# MOTOR_DRV.net
KiCad netlist of a schematic drawn in Altium Designer
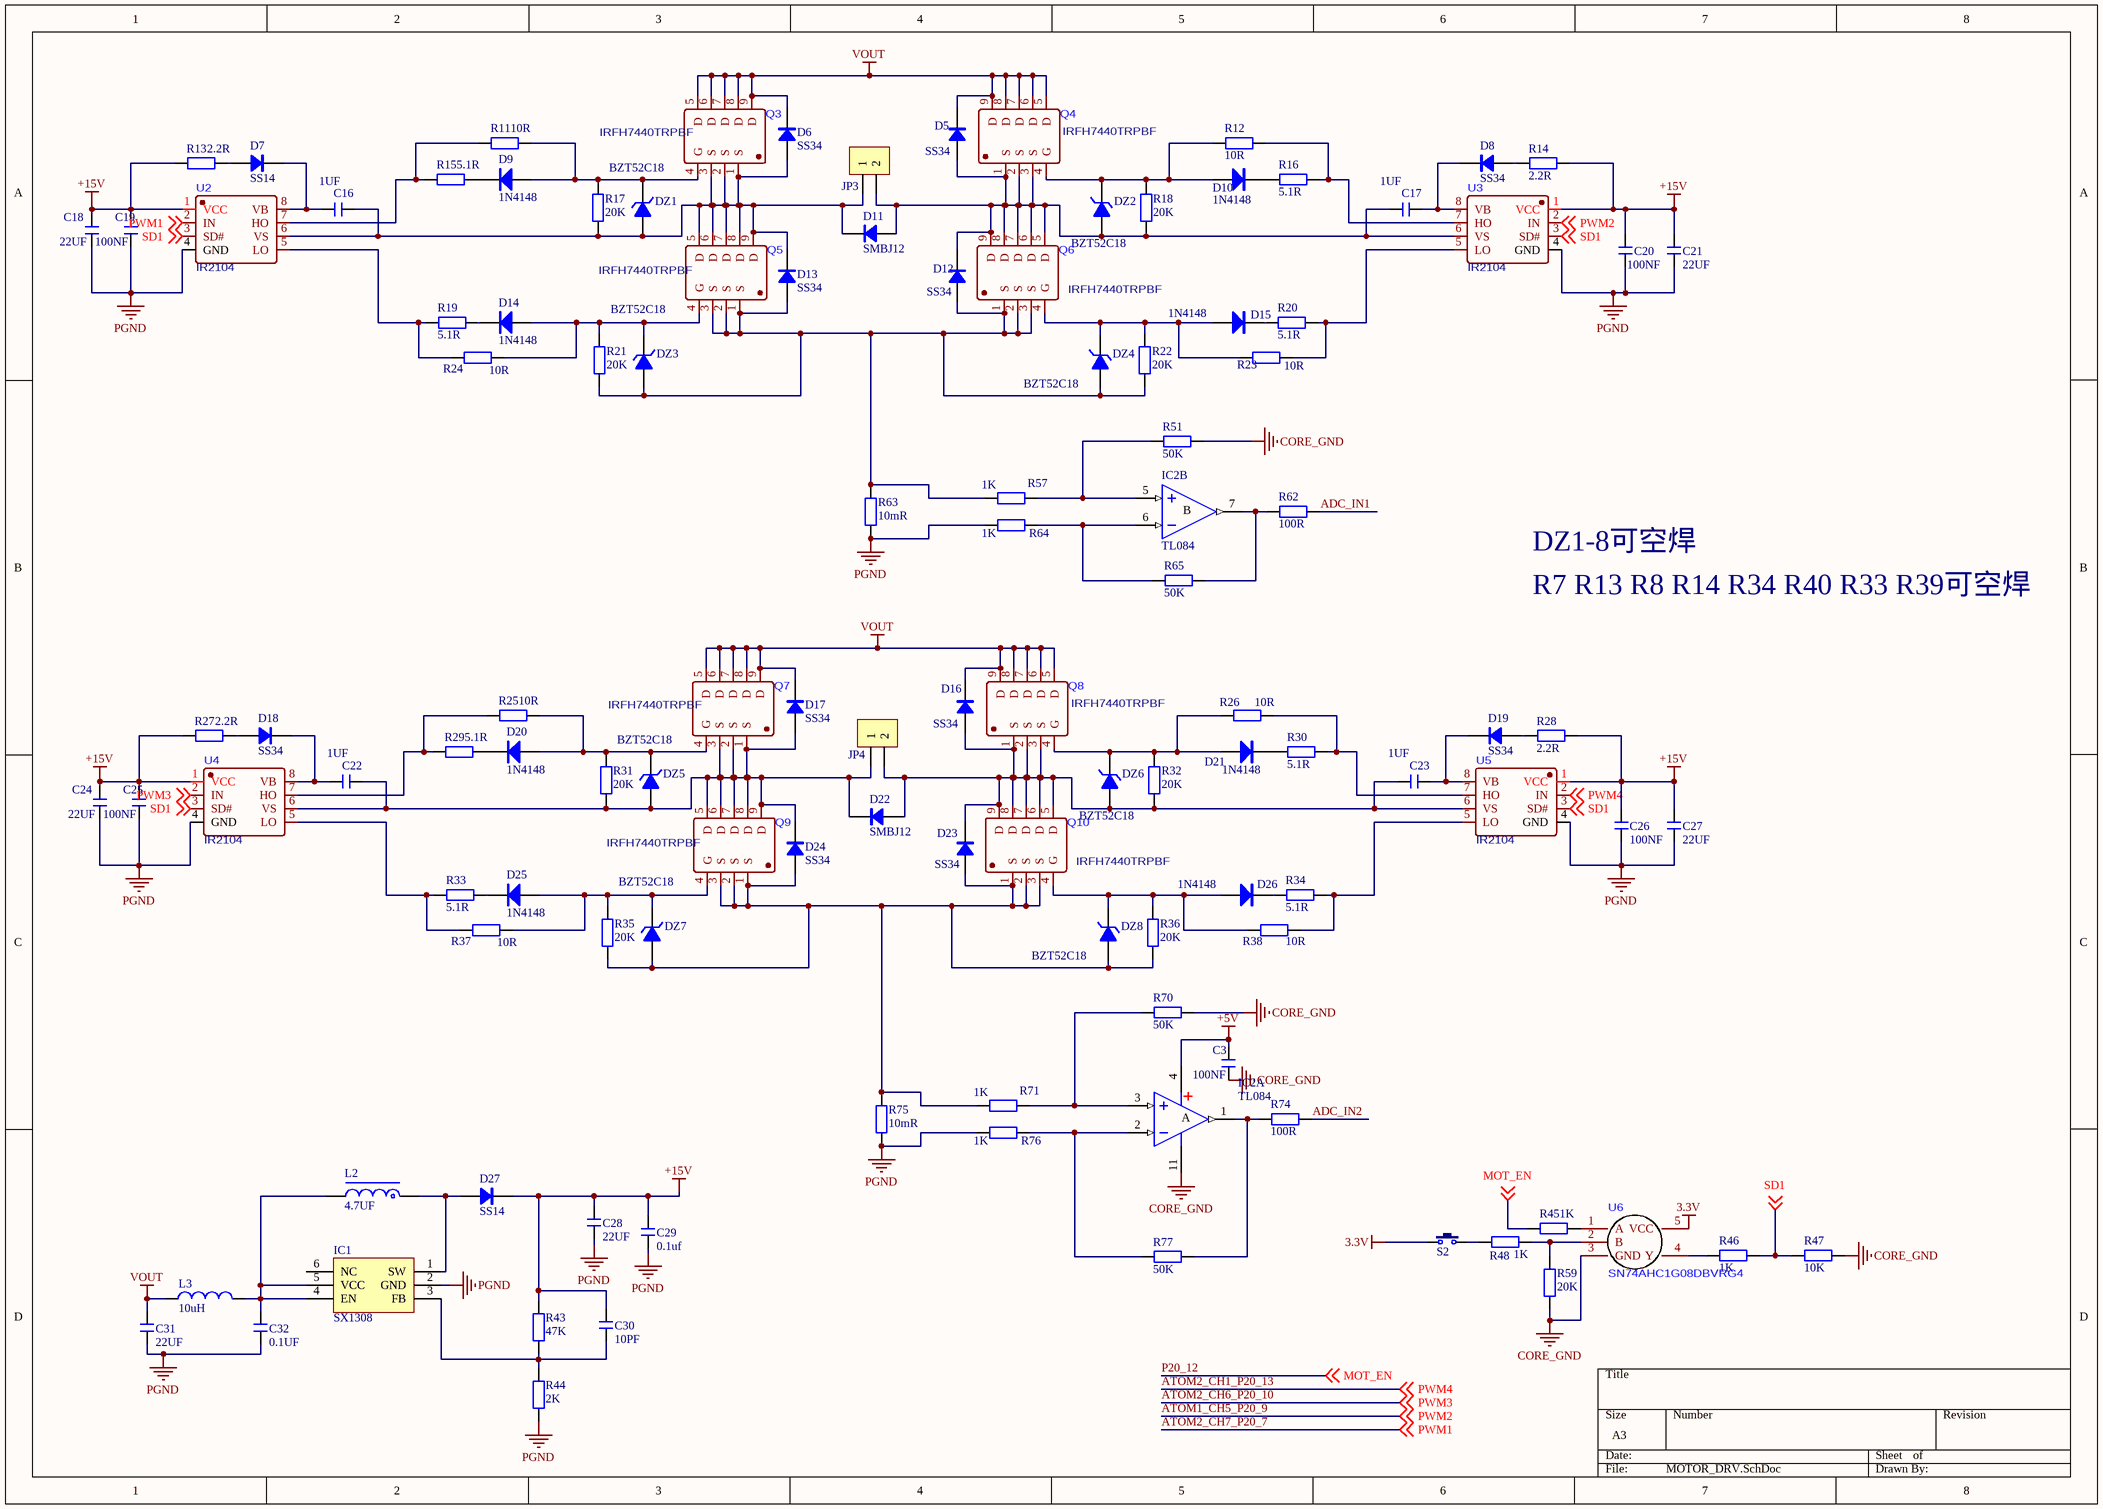
[diagram p0: MOTOR_DRV.SchDoc]

(export (version "E")
  (design (tool "Eeschema 10.0.6"))
  (components
    (comp (ref "C3")
      (value "100NF")
      (footprint "C 0805_L")
      (description "无极性贴片电容")
      (fields (field (name "版权归属") "源创客"))
      (libsource (lib "3.1   - 电阻-电容-电感") (part "C"))
    )
    (comp (ref "C16")
      (value "1UF")
      (footprint "C 1206_L")
      (description "无极性贴片电容")
      (fields (field (name "版权归属") "源创客"))
      (libsource (lib "3.1   - 电阻-电容-电感") (part "C"))
    )
    (comp (ref "C17")
      (value "1UF")
      (footprint "C 1206_L")
      (description "无极性贴片电容")
      (fields (field (name "版权归属") "源创客"))
      (libsource (lib "3.1   - 电阻-电容-电感") (part "C"))
    )
    (comp (ref "C18")
      (value "22UF")
      (footprint "C 0805_L")
      (description "无极性贴片电容")
      (fields (field (name "版权归属") "源创客"))
      (libsource (lib "3.1   - 电阻-电容-电感") (part "C"))
    )
    (comp (ref "C19")
      (value "100NF")
      (footprint "C 0805_L")
      (description "无极性贴片电容")
      (fields (field (name "版权归属") "源创客"))
      (libsource (lib "3.1   - 电阻-电容-电感") (part "C"))
    )
    (comp (ref "C20")
      (value "100NF")
      (footprint "C 0805_L")
      (description "无极性贴片电容")
      (fields (field (name "版权归属") "源创客"))
      (libsource (lib "3.1   - 电阻-电容-电感") (part "C"))
    )
    (comp (ref "C21")
      (value "22UF")
      (footprint "C 0805_L")
      (description "无极性贴片电容")
      (fields (field (name "版权归属") "源创客"))
      (libsource (lib "3.1   - 电阻-电容-电感") (part "C"))
    )
    (comp (ref "C22")
      (value "1UF")
      (footprint "C 1206_L")
      (description "无极性贴片电容")
      (fields (field (name "版权归属") "源创客"))
      (libsource (lib "3.1   - 电阻-电容-电感") (part "C"))
    )
    (comp (ref "C23")
      (value "1UF")
      (footprint "C 1206_L")
      (description "无极性贴片电容")
      (fields (field (name "版权归属") "源创客"))
      (libsource (lib "3.1   - 电阻-电容-电感") (part "C"))
    )
    (comp (ref "C24")
      (value "22UF")
      (footprint "C 0805_L")
      (description "无极性贴片电容")
      (fields (field (name "版权归属") "源创客"))
      (libsource (lib "3.1   - 电阻-电容-电感") (part "C"))
    )
    (comp (ref "C25")
      (value "100NF")
      (footprint "C 0805_L")
      (description "无极性贴片电容")
      (fields (field (name "版权归属") "源创客"))
      (libsource (lib "3.1   - 电阻-电容-电感") (part "C"))
    )
    (comp (ref "C26")
      (value "100NF")
      (footprint "C 0805_L")
      (description "无极性贴片电容")
      (fields (field (name "版权归属") "源创客"))
      (libsource (lib "3.1   - 电阻-电容-电感") (part "C"))
    )
    (comp (ref "C27")
      (value "22UF")
      (footprint "C 0805_L")
      (description "无极性贴片电容")
      (fields (field (name "版权归属") "源创客"))
      (libsource (lib "3.1   - 电阻-电容-电感") (part "C"))
    )
    (comp (ref "C28")
      (value "22UF")
      (footprint "C 1206_L")
      (description "无极性贴片电容")
      (fields (field (name "版权归属") "源创客"))
      (libsource (lib "3.1   - 电阻-电容-电感") (part "C"))
    )
    (comp (ref "C29")
      (value "0.1uf")
      (footprint "C 0805_L")
      (description "无极性贴片电容")
      (fields (field (name "版权归属") "源创客"))
      (libsource (lib "3.1   - 电阻-电容-电感") (part "C"))
    )
    (comp (ref "C30")
      (value "10PF")
      (footprint "C 0603_L")
      (description "无极性贴片电容")
      (fields (field (name "版权归属") "源创客"))
      (libsource (lib "3.1   - 电阻-电容-电感") (part "C"))
    )
    (comp (ref "C31")
      (value "22UF")
      (footprint "C 1206_L")
      (description "无极性贴片电容")
      (fields (field (name "版权归属") "源创客"))
      (libsource (lib "3.1   - 电阻-电容-电感") (part "C"))
    )
    (comp (ref "C32")
      (value "0.1UF")
      (footprint "C 0805_L")
      (description "无极性贴片电容")
      (fields (field (name "版权归属") "源创客"))
      (libsource (lib "3.1   - 电阻-电容-电感") (part "C"))
    )
    (comp (ref "D5")
      (value "SS34")
      (footprint "SMA")
      (description "肖特基二极管")
      (fields (field (name "版权归属") "源创客"))
      (libsource (lib "8.1   - 二极管-整流桥") (part "SS34"))
    )
    (comp (ref "D6")
      (value "SS34")
      (footprint "SMA")
      (description "肖特基二极管")
      (fields (field (name "版权归属") "源创客"))
      (libsource (lib "8.1   - 二极管-整流桥") (part "SS34"))
    )
    (comp (ref "D7")
      (value "SS14")
      (footprint "SOD-123")
      (description "肖特基二极管")
      (fields (field (name "版权归属") "源创客"))
      (libsource (lib "8.1   - 二极管-整流桥") (part "SS34"))
    )
    (comp (ref "D8")
      (value "SS34")
      (footprint "SOD-123")
      (description "肖特基二极管")
      (fields (field (name "版权归属") "源创客"))
      (libsource (lib "8.1   - 二极管-整流桥") (part "SS34"))
    )
    (comp (ref "D9")
      (value "1N4148")
      (footprint "SOD-323")
      (description "高速开关二极管")
      (fields (field (name "版权归属") "源创客"))
      (libsource (lib "8.1   - 二极管-整流桥") (part "1N4148"))
    )
    (comp (ref "D10")
      (value "1N4148")
      (footprint "SOD-323")
      (description "高速开关二极管")
      (fields (field (name "版权归属") "源创客"))
      (libsource (lib "8.1   - 二极管-整流桥") (part "1N4148"))
    )
    (comp (ref "D11")
      (value "SMBJ12")
      (footprint "SMA")
      (description "肖特基二极管")
      (fields (field (name "版权归属") "源创客"))
      (libsource (lib "8.1   - 二极管-整流桥") (part "SS34"))
    )
    (comp (ref "D12")
      (value "SS34")
      (footprint "SMA")
      (description "肖特基二极管")
      (fields (field (name "版权归属") "源创客"))
      (libsource (lib "8.1   - 二极管-整流桥") (part "SS34"))
    )
    (comp (ref "D13")
      (value "SS34")
      (footprint "SMA")
      (description "肖特基二极管")
      (fields (field (name "版权归属") "源创客"))
      (libsource (lib "8.1   - 二极管-整流桥") (part "SS34"))
    )
    (comp (ref "D14")
      (value "1N4148")
      (footprint "SOD-323")
      (description "高速开关二极管")
      (fields (field (name "版权归属") "源创客"))
      (libsource (lib "8.1   - 二极管-整流桥") (part "1N4148"))
    )
    (comp (ref "D15")
      (value "1N4148")
      (footprint "SOD-323")
      (description "高速开关二极管")
      (fields (field (name "版权归属") "源创客"))
      (libsource (lib "8.1   - 二极管-整流桥") (part "1N4148"))
    )
    (comp (ref "D16")
      (value "SS34")
      (footprint "SMA")
      (description "肖特基二极管")
      (fields (field (name "版权归属") "源创客"))
      (libsource (lib "8.1   - 二极管-整流桥") (part "SS34"))
    )
    (comp (ref "D17")
      (value "SS34")
      (footprint "SMA")
      (description "肖特基二极管")
      (fields (field (name "版权归属") "源创客"))
      (libsource (lib "8.1   - 二极管-整流桥") (part "SS34"))
    )
    (comp (ref "D18")
      (value "SS34")
      (footprint "SOD-123")
      (description "肖特基二极管")
      (fields (field (name "版权归属") "源创客"))
      (libsource (lib "8.1   - 二极管-整流桥") (part "SS34"))
    )
    (comp (ref "D19")
      (value "SS34")
      (footprint "SOD-123")
      (description "肖特基二极管")
      (fields (field (name "版权归属") "源创客"))
      (libsource (lib "8.1   - 二极管-整流桥") (part "SS34"))
    )
    (comp (ref "D20")
      (value "1N4148")
      (footprint "SOD-323")
      (description "高速开关二极管")
      (fields (field (name "版权归属") "源创客"))
      (libsource (lib "8.1   - 二极管-整流桥") (part "1N4148"))
    )
    (comp (ref "D21")
      (value "1N4148")
      (footprint "SOD-323")
      (description "高速开关二极管")
      (fields (field (name "版权归属") "源创客"))
      (libsource (lib "8.1   - 二极管-整流桥") (part "1N4148"))
    )
    (comp (ref "D22")
      (value "SMBJ12")
      (footprint "SMA")
      (description "肖特基二极管")
      (fields (field (name "版权归属") "源创客"))
      (libsource (lib "8.1   - 二极管-整流桥") (part "SS34"))
    )
    (comp (ref "D23")
      (value "SS34")
      (footprint "SMA")
      (description "肖特基二极管")
      (fields (field (name "版权归属") "源创客"))
      (libsource (lib "8.1   - 二极管-整流桥") (part "SS34"))
    )
    (comp (ref "D24")
      (value "SS34")
      (footprint "SMA")
      (description "肖特基二极管")
      (fields (field (name "版权归属") "源创客"))
      (libsource (lib "8.1   - 二极管-整流桥") (part "SS34"))
    )
    (comp (ref "D25")
      (value "1N4148")
      (footprint "SOD-323")
      (description "高速开关二极管")
      (fields (field (name "版权归属") "源创客"))
      (libsource (lib "8.1   - 二极管-整流桥") (part "1N4148"))
    )
    (comp (ref "D26")
      (value "1N4148")
      (footprint "SOD-323")
      (description "高速开关二极管")
      (fields (field (name "版权归属") "源创客"))
      (libsource (lib "8.1   - 二极管-整流桥") (part "1N4148"))
    )
    (comp (ref "D27")
      (value "SS14")
      (footprint "SOD-123")
      (description "肖特基二极管")
      (fields (field (name "版权归属") "源创客"))
      (libsource (lib "8.1   - 二极管-整流桥") (part "SS24"))
    )
    (comp (ref "DZ1")
      (value "BZT52C18")
      (footprint "SOD-323")
      (description "18V稳压管")
      (fields (field (name "版权归属") "源创客"))
      (libsource (lib "8.1   - 二极管-整流桥") (part "1N4102"))
    )
    (comp (ref "DZ2")
      (value "BZT52C18")
      (footprint "SOD-323")
      (description "18V稳压管")
      (fields (field (name "版权归属") "源创客"))
      (libsource (lib "8.1   - 二极管-整流桥") (part "1N4102"))
    )
    (comp (ref "DZ3")
      (value "BZT52C18")
      (footprint "SOD-323")
      (description "18V稳压管")
      (fields (field (name "版权归属") "源创客"))
      (libsource (lib "8.1   - 二极管-整流桥") (part "1N4102"))
    )
    (comp (ref "DZ4")
      (value "BZT52C18")
      (footprint "SOD-323")
      (description "18V稳压管")
      (fields (field (name "版权归属") "源创客"))
      (libsource (lib "8.1   - 二极管-整流桥") (part "1N4102"))
    )
    (comp (ref "DZ5")
      (value "BZT52C18")
      (footprint "SOD-323")
      (description "18V稳压管")
      (fields (field (name "版权归属") "源创客"))
      (libsource (lib "8.1   - 二极管-整流桥") (part "1N4102"))
    )
    (comp (ref "DZ6")
      (value "BZT52C18")
      (footprint "SOD-323")
      (description "18V稳压管")
      (fields (field (name "版权归属") "源创客"))
      (libsource (lib "8.1   - 二极管-整流桥") (part "1N4102"))
    )
    (comp (ref "DZ7")
      (value "BZT52C18")
      (footprint "SOD-323")
      (description "18V稳压管")
      (fields (field (name "版权归属") "源创客"))
      (libsource (lib "8.1   - 二极管-整流桥") (part "1N4102"))
    )
    (comp (ref "DZ8")
      (value "BZT52C18")
      (footprint "SOD-323")
      (description "18V稳压管")
      (fields (field (name "版权归属") "源创客"))
      (libsource (lib "8.1   - 二极管-整流桥") (part "1N4102"))
    )
    (comp (ref "IC1")
      (value "SX1308")
      (footprint "SOT23-6N")
      (description "可调升压芯片")
      (fields (field (name "版权归属") "源创客"))
      (libsource (lib "1.3   - 电源类芯片") (part "SX1308"))
    )
    (comp (ref "IC2")
      (value "TL084")
      (footprint "SOP14_N")
      (description "4路运放")
      (fields (field (name "版权归属") "源创客"))
      (libsource (lib "1.5   - 运放-功放") (part "TL084"))
    )
    (comp (ref "JP3")
      (value "HDR-1X2")
      (footprint "KF2EDGK5.08-LI-2P")
      (description "2P接插件")
      (fields (field (name "版权归属") "源创客"))
      (libsource (lib "4.11 - 接插件-脚距5.08") (part "Header 2"))
    )
    (comp (ref "JP4")
      (value "HDR-1X2")
      (footprint "KF2EDGK5.08-LI-2P")
      (description "2P接插件")
      (fields (field (name "版权归属") "源创客"))
      (libsource (lib "4.11 - 接插件-脚距5.08") (part "Header 2"))
    )
    (comp (ref "L2")
      (value "4.7UF")
      (footprint "L-SMD-0420")
      (description "功率屏蔽电感")
      (fields (field (name "版权归属") "源创客"))
      (libsource (lib "3.1   - 电阻-电容-电感") (part "L-CDRH"))
    )
    (comp (ref "L3")
      (value "10uH")
      (footprint "L 0805_L")
      (description "小功率贴片电感")
      (fields (field (name "版权归属") "源创客"))
      (libsource (lib "3.1   - 电阻-电容-电感") (part "L"))
    )
    (comp (ref "Q3")
      (value "IRFH7440TRPBF")
      (footprint "PQFN-8P_L5.8-W4.9-P1.27-LS6.0-BL")
      (libsource (lib "IRFH7440TRPBF") (part "IRFH7440TRPBF"))
    )
    (comp (ref "Q4")
      (value "IRFH7440TRPBF")
      (footprint "PQFN-8P_L5.8-W4.9-P1.27-LS6.0-BL")
      (libsource (lib "IRFH7440TRPBF") (part "IRFH7440TRPBF"))
    )
    (comp (ref "Q5")
      (value "IRFH7440TRPBF")
      (footprint "PQFN-8P_L5.8-W4.9-P1.27-LS6.0-BL")
      (libsource (lib "IRFH7440TRPBF") (part "IRFH7440TRPBF"))
    )
    (comp (ref "Q6")
      (value "IRFH7440TRPBF")
      (footprint "PQFN-8P_L5.8-W4.9-P1.27-LS6.0-BL")
      (libsource (lib "IRFH7440TRPBF") (part "IRFH7440TRPBF"))
    )
    (comp (ref "Q7")
      (value "IRFH7440TRPBF")
      (footprint "PQFN-8P_L5.8-W4.9-P1.27-LS6.0-BL")
      (libsource (lib "IRFH7440TRPBF") (part "IRFH7440TRPBF"))
    )
    (comp (ref "Q8")
      (value "IRFH7440TRPBF")
      (footprint "PQFN-8P_L5.8-W4.9-P1.27-LS6.0-BL")
      (libsource (lib "IRFH7440TRPBF") (part "IRFH7440TRPBF"))
    )
    (comp (ref "Q9")
      (value "IRFH7440TRPBF")
      (footprint "PQFN-8P_L5.8-W4.9-P1.27-LS6.0-BL")
      (libsource (lib "IRFH7440TRPBF") (part "IRFH7440TRPBF"))
    )
    (comp (ref "Q10")
      (value "IRFH7440TRPBF")
      (footprint "PQFN-8P_L5.8-W4.9-P1.27-LS6.0-BL")
      (libsource (lib "IRFH7440TRPBF") (part "IRFH7440TRPBF"))
    )
    (comp (ref "R11")
      (value "10R")
      (footprint "R 0805_L")
      (description "贴片电阻")
      (fields (field (name "版权归属") "源创客"))
      (libsource (lib "3.1   - 电阻-电容-电感") (part "R"))
    )
    (comp (ref "R12")
      (value "10R")
      (footprint "R 0805_L")
      (description "贴片电阻")
      (fields (field (name "版权归属") "源创客"))
      (libsource (lib "3.1   - 电阻-电容-电感") (part "R"))
    )
    (comp (ref "R13")
      (value "2.2R")
      (footprint "R 0805_L")
      (description "贴片电阻")
      (fields (field (name "版权归属") "源创客"))
      (libsource (lib "3.1   - 电阻-电容-电感") (part "R"))
    )
    (comp (ref "R14")
      (value "2.2R")
      (footprint "R 0805_L")
      (description "贴片电阻")
      (fields (field (name "版权归属") "源创客"))
      (libsource (lib "3.1   - 电阻-电容-电感") (part "R"))
    )
    (comp (ref "R15")
      (value "5.1R")
      (footprint "R 0805_L")
      (description "贴片电阻")
      (fields (field (name "版权归属") "源创客"))
      (libsource (lib "3.1   - 电阻-电容-电感") (part "R"))
    )
    (comp (ref "R16")
      (value "5.1R")
      (footprint "R 0805_L")
      (description "贴片电阻")
      (fields (field (name "版权归属") "源创客"))
      (libsource (lib "3.1   - 电阻-电容-电感") (part "R"))
    )
    (comp (ref "R17")
      (value "20K")
      (footprint "R 0805_L")
      (description "贴片电阻")
      (fields (field (name "版权归属") "源创客"))
      (libsource (lib "3.1   - 电阻-电容-电感") (part "R"))
    )
    (comp (ref "R18")
      (value "20K")
      (footprint "R 0805_L")
      (description "贴片电阻")
      (fields (field (name "版权归属") "源创客"))
      (libsource (lib "3.1   - 电阻-电容-电感") (part "R"))
    )
    (comp (ref "R19")
      (value "5.1R")
      (footprint "R 0805_L")
      (description "贴片电阻")
      (fields (field (name "版权归属") "源创客"))
      (libsource (lib "3.1   - 电阻-电容-电感") (part "R"))
    )
    (comp (ref "R20")
      (value "5.1R")
      (footprint "R 0805_L")
      (description "贴片电阻")
      (fields (field (name "版权归属") "源创客"))
      (libsource (lib "3.1   - 电阻-电容-电感") (part "R"))
    )
    (comp (ref "R21")
      (value "20K")
      (footprint "R 0805_L")
      (description "贴片电阻")
      (fields (field (name "版权归属") "源创客"))
      (libsource (lib "3.1   - 电阻-电容-电感") (part "R"))
    )
    (comp (ref "R22")
      (value "20K")
      (footprint "R 0805_L")
      (description "贴片电阻")
      (fields (field (name "版权归属") "源创客"))
      (libsource (lib "3.1   - 电阻-电容-电感") (part "R"))
    )
    (comp (ref "R23")
      (value "10R")
      (footprint "R 0805_L")
      (description "贴片电阻")
      (fields (field (name "版权归属") "源创客"))
      (libsource (lib "3.1   - 电阻-电容-电感") (part "R"))
    )
    (comp (ref "R24")
      (value "10R")
      (footprint "R 0805_L")
      (description "贴片电阻")
      (fields (field (name "版权归属") "源创客"))
      (libsource (lib "3.1   - 电阻-电容-电感") (part "R"))
    )
    (comp (ref "R25")
      (value "10R")
      (footprint "R 0805_L")
      (description "贴片电阻")
      (fields (field (name "版权归属") "源创客"))
      (libsource (lib "3.1   - 电阻-电容-电感") (part "R"))
    )
    (comp (ref "R26")
      (value "10R")
      (footprint "R 0805_L")
      (description "贴片电阻")
      (fields (field (name "版权归属") "源创客"))
      (libsource (lib "3.1   - 电阻-电容-电感") (part "R"))
    )
    (comp (ref "R27")
      (value "2.2R")
      (footprint "R 0805_L")
      (description "贴片电阻")
      (fields (field (name "版权归属") "源创客"))
      (libsource (lib "3.1   - 电阻-电容-电感") (part "R"))
    )
    (comp (ref "R28")
      (value "2.2R")
      (footprint "R 0805_L")
      (description "贴片电阻")
      (fields (field (name "版权归属") "源创客"))
      (libsource (lib "3.1   - 电阻-电容-电感") (part "R"))
    )
    (comp (ref "R29")
      (value "5.1R")
      (footprint "R 0805_L")
      (description "贴片电阻")
      (fields (field (name "版权归属") "源创客"))
      (libsource (lib "3.1   - 电阻-电容-电感") (part "R"))
    )
    (comp (ref "R30")
      (value "5.1R")
      (footprint "R 0805_L")
      (description "贴片电阻")
      (fields (field (name "版权归属") "源创客"))
      (libsource (lib "3.1   - 电阻-电容-电感") (part "R"))
    )
    (comp (ref "R31")
      (value "20K")
      (footprint "R 0805_L")
      (description "贴片电阻")
      (fields (field (name "版权归属") "源创客"))
      (libsource (lib "3.1   - 电阻-电容-电感") (part "R"))
    )
    (comp (ref "R32")
      (value "20K")
      (footprint "R 0805_L")
      (description "贴片电阻")
      (fields (field (name "版权归属") "源创客"))
      (libsource (lib "3.1   - 电阻-电容-电感") (part "R"))
    )
    (comp (ref "R33")
      (value "5.1R")
      (footprint "R 0805_L")
      (description "贴片电阻")
      (fields (field (name "版权归属") "源创客"))
      (libsource (lib "3.1   - 电阻-电容-电感") (part "R"))
    )
    (comp (ref "R34")
      (value "5.1R")
      (footprint "R 0805_L")
      (description "贴片电阻")
      (fields (field (name "版权归属") "源创客"))
      (libsource (lib "3.1   - 电阻-电容-电感") (part "R"))
    )
    (comp (ref "R35")
      (value "20K")
      (footprint "R 0805_L")
      (description "贴片电阻")
      (fields (field (name "版权归属") "源创客"))
      (libsource (lib "3.1   - 电阻-电容-电感") (part "R"))
    )
    (comp (ref "R36")
      (value "20K")
      (footprint "R 0805_L")
      (description "贴片电阻")
      (fields (field (name "版权归属") "源创客"))
      (libsource (lib "3.1   - 电阻-电容-电感") (part "R"))
    )
    (comp (ref "R37")
      (value "10R")
      (footprint "R 0805_L")
      (description "贴片电阻")
      (fields (field (name "版权归属") "源创客"))
      (libsource (lib "3.1   - 电阻-电容-电感") (part "R"))
    )
    (comp (ref "R38")
      (value "10R")
      (footprint "R 0805_L")
      (description "贴片电阻")
      (fields (field (name "版权归属") "源创客"))
      (libsource (lib "3.1   - 电阻-电容-电感") (part "R"))
    )
    (comp (ref "R43")
      (value "47K")
      (footprint "R 0805_L")
      (description "贴片电阻")
      (fields (field (name "版权归属") "源创客"))
      (libsource (lib "3.1   - 电阻-电容-电感") (part "R"))
    )
    (comp (ref "R44")
      (value "2K")
      (footprint "R 0805_L")
      (description "贴片电阻")
      (fields (field (name "版权归属") "源创客"))
      (libsource (lib "3.1   - 电阻-电容-电感") (part "R"))
    )
    (comp (ref "R45")
      (value "1K")
      (footprint "R 0805_L")
      (description "贴片电阻")
      (fields (field (name "版权归属") "源创客"))
      (libsource (lib "3.1   - 电阻-电容-电感") (part "R"))
    )
    (comp (ref "R46")
      (value "1K")
      (footprint "R 0805_L")
      (description "贴片电阻")
      (fields (field (name "版权归属") "源创客"))
      (libsource (lib "3.1   - 电阻-电容-电感") (part "R"))
    )
    (comp (ref "R47")
      (value "10K")
      (footprint "R 0805_L")
      (description "贴片电阻")
      (fields (field (name "版权归属") "源创客"))
      (libsource (lib "3.1   - 电阻-电容-电感") (part "R"))
    )
    (comp (ref "R48")
      (value "1K")
      (footprint "R 0805_L")
      (description "贴片电阻")
      (fields (field (name "版权归属") "源创客"))
      (libsource (lib "3.1   - 电阻-电容-电感") (part "R"))
    )
    (comp (ref "R51")
      (value "50K")
      (footprint "R 0805_L")
      (description "贴片电阻")
      (fields (field (name "版权归属") "源创客"))
      (libsource (lib "3.1   - 电阻-电容-电感") (part "R"))
    )
    (comp (ref "R57")
      (value "1K")
      (footprint "R 0805_L")
      (description "贴片电阻")
      (fields (field (name "版权归属") "源创客"))
      (libsource (lib "3.1   - 电阻-电容-电感") (part "R"))
    )
    (comp (ref "R59")
      (value "20K")
      (footprint "R 0805_L")
      (description "贴片电阻")
      (fields (field (name "版权归属") "源创客"))
      (libsource (lib "3.1   - 电阻-电容-电感") (part "R"))
    )
    (comp (ref "R62")
      (value "100R")
      (footprint "R 0805_L")
      (description "贴片电阻")
      (fields (field (name "版权归属") "源创客"))
      (libsource (lib "3.1   - 电阻-电容-电感") (part "R"))
    )
    (comp (ref "R63")
      (value "10mR")
      (footprint "R 2512_M")
      (description "贴片电阻")
      (fields (field (name "版权归属") "源创客"))
      (libsource (lib "3.1   - 电阻-电容-电感") (part "R"))
    )
    (comp (ref "R64")
      (value "1K")
      (footprint "R 0805_L")
      (description "贴片电阻")
      (fields (field (name "版权归属") "源创客"))
      (libsource (lib "3.1   - 电阻-电容-电感") (part "R"))
    )
    (comp (ref "R65")
      (value "50K")
      (footprint "R 0805_L")
      (description "贴片电阻")
      (fields (field (name "版权归属") "源创客"))
      (libsource (lib "3.1   - 电阻-电容-电感") (part "R"))
    )
    (comp (ref "R70")
      (value "50K")
      (footprint "R 0805_L")
      (description "贴片电阻")
      (fields (field (name "版权归属") "源创客"))
      (libsource (lib "3.1   - 电阻-电容-电感") (part "R"))
    )
    (comp (ref "R71")
      (value "1K")
      (footprint "R 0805_L")
      (description "贴片电阻")
      (fields (field (name "版权归属") "源创客"))
      (libsource (lib "3.1   - 电阻-电容-电感") (part "R"))
    )
    (comp (ref "R74")
      (value "100R")
      (footprint "R 0805_L")
      (description "贴片电阻")
      (fields (field (name "版权归属") "源创客"))
      (libsource (lib "3.1   - 电阻-电容-电感") (part "R"))
    )
    (comp (ref "R75")
      (value "10mR")
      (footprint "R 2512_M")
      (description "贴片电阻")
      (fields (field (name "版权归属") "源创客"))
      (libsource (lib "3.1   - 电阻-电容-电感") (part "R"))
    )
    (comp (ref "R76")
      (value "1K")
      (footprint "R 0805_L")
      (description "贴片电阻")
      (fields (field (name "版权归属") "源创客"))
      (libsource (lib "3.1   - 电阻-电容-电感") (part "R"))
    )
    (comp (ref "R77")
      (value "50K")
      (footprint "R 0805_L")
      (description "贴片电阻")
      (fields (field (name "版权归属") "源创客"))
      (libsource (lib "3.1   - 电阻-电容-电感") (part "R"))
    )
    (comp (ref "S2")
      (value "6x6x5")
      (footprint "KEY-TH_CN-KCD11")
      (description "2脚直插6x6轻触开关")
      (fields (field (name "版权归属") "源创客"))
      (libsource (lib "5.1   - 按键-开关") (part "TSW DIP-2Pin-6x6"))
    )
    (comp (ref "U2") (value "IR2104") (footprint "SOP8_M") (libsource (lib "EG2104") (part "EG2104")))
    (comp (ref "U3") (value "IR2104") (footprint "SOP8_M") (libsource (lib "EG2104") (part "EG2104")))
    (comp (ref "U4") (value "IR2104") (footprint "SOP8_M") (libsource (lib "EG2104") (part "EG2104")))
    (comp (ref "U5") (value "IR2104") (footprint "SOP8_M") (libsource (lib "EG2104") (part "EG2104")))
    (comp (ref "U6")
      (value "SN74AHC1G08DBVRG4")
      (footprint "SOT23-5L")
      (libsource (lib "SN74AHC1G08DBVRG4") (part "SN74AHC1G08DBVRG4"))
    )
  )
  (nets
    (net (code "1") (name "+5V") (class "Default")
      (node (ref "C3") (pin "2") (pinfunction "2_2") (pintype "passive"))
      (node (ref "IC2") (pin "4") (pinfunction "V+_4") (pintype "power_in"))
    )
    (net (code "2") (name "+15V") (class "Default")
      (node (ref "C18") (pin "2") (pinfunction "2_2") (pintype "passive"))
      (node (ref "C19") (pin "2") (pinfunction "2_2") (pintype "passive"))
      (node (ref "C20") (pin "2") (pinfunction "2_2") (pintype "passive"))
      (node (ref "C21") (pin "2") (pinfunction "2_2") (pintype "passive"))
      (node (ref "C24") (pin "2") (pinfunction "2_2") (pintype "passive"))
      (node (ref "C25") (pin "2") (pinfunction "2_2") (pintype "passive"))
      (node (ref "C26") (pin "2") (pinfunction "2_2") (pintype "passive"))
      (node (ref "C27") (pin "2") (pinfunction "2_2") (pintype "passive"))
      (node (ref "C28") (pin "1") (pinfunction "1_1") (pintype "passive"))
      (node (ref "C29") (pin "1") (pinfunction "1_1") (pintype "passive"))
      (node (ref "C30") (pin "1") (pinfunction "1_1") (pintype "passive"))
      (node (ref "D27") (pin "2") (pinfunction "K_2") (pintype "passive"))
      (node (ref "R13") (pin "1") (pinfunction "1_1") (pintype "passive"))
      (node (ref "R14") (pin "1") (pinfunction "1_1") (pintype "passive"))
      (node (ref "R27") (pin "1") (pinfunction "1_1") (pintype "passive"))
      (node (ref "R28") (pin "1") (pinfunction "1_1") (pintype "passive"))
      (node (ref "R43") (pin "1") (pinfunction "1_1") (pintype "passive"))
      (node (ref "U2") (pin "1") (pinfunction "VCC_1") (pintype "passive"))
      (node (ref "U3") (pin "1") (pinfunction "VCC_1") (pintype "passive"))
      (node (ref "U4") (pin "1") (pinfunction "VCC_1") (pintype "passive"))
      (node (ref "U5") (pin "1") (pinfunction "VCC_1") (pintype "passive"))
    )
    (net (code "3") (name "/ADC_IN1") (class "Default")
      (node (ref "R62") (pin "1") (pinfunction "1_1") (pintype "passive"))
    )
    (net (code "4") (name "/ADC_IN2") (class "Default")
      (node (ref "R74") (pin "1") (pinfunction "1_1") (pintype "passive"))
    )
    (net (code "5") (name "3.3V") (class "Default")
      (node (ref "S2") (pin "1") (pinfunction "1_1") (pintype "passive"))
      (node (ref "U6") (pin "5") (pinfunction "VCC_5") (pintype "passive"))
    )
    (net (code "6") (name "CORE_GND") (class "Default")
      (node (ref "C3") (pin "1") (pinfunction "1_1") (pintype "passive"))
      (node (ref "IC2") (pin "11") (pinfunction "V-_11") (pintype "power_in"))
      (node (ref "R47") (pin "2") (pinfunction "2_2") (pintype "passive"))
      (node (ref "R51") (pin "1") (pinfunction "1_1") (pintype "passive"))
      (node (ref "R59") (pin "2") (pinfunction "2_2") (pintype "passive"))
      (node (ref "R70") (pin "1") (pinfunction "1_1") (pintype "passive"))
      (node (ref "U6") (pin "3") (pinfunction "GND_3") (pintype "passive"))
    )
    (net (code "7") (name "MOT_EN") (class "Default")
      (node (ref "R45") (pin "2") (pinfunction "2_2") (pintype "passive"))
    )
    (net (code "8") (name "Net-(D7-A)") (class "Default")
      (node (ref "D7") (pin "1") (pinfunction "A_1") (pintype "passive"))
      (node (ref "R13") (pin "2") (pinfunction "2_2") (pintype "passive"))
    )
    (net (code "9") (name "Net-(D7-K)") (class "Default")
      (node (ref "C16") (pin "2") (pinfunction "2_2") (pintype "passive"))
      (node (ref "D7") (pin "2") (pinfunction "K_2") (pintype "passive"))
      (node (ref "U2") (pin "8") (pinfunction "VB_8") (pintype "passive"))
    )
    (net (code "10") (name "Net-(D8-A)") (class "Default")
      (node (ref "D8") (pin "1") (pinfunction "A_1") (pintype "passive"))
      (node (ref "R14") (pin "2") (pinfunction "2_2") (pintype "passive"))
    )
    (net (code "11") (name "Net-(D8-K)") (class "Default")
      (node (ref "C17") (pin "2") (pinfunction "2_2") (pintype "passive"))
      (node (ref "D8") (pin "2") (pinfunction "K_2") (pintype "passive"))
      (node (ref "U3") (pin "8") (pinfunction "VB_8") (pintype "passive"))
    )
    (net (code "12") (name "Net-(D9-A)") (class "Default")
      (node (ref "D9") (pin "1") (pinfunction "A_1") (pintype "passive"))
      (node (ref "DZ1") (pin "2") (pinfunction "K_2") (pintype "passive"))
      (node (ref "Q3") (pin "4") (pinfunction "G_4") (pintype "passive"))
      (node (ref "R11") (pin "2") (pinfunction "2_2") (pintype "passive"))
      (node (ref "R17") (pin "2") (pinfunction "2_2") (pintype "passive"))
    )
    (net (code "13") (name "Net-(D9-K)") (class "Default")
      (node (ref "D9") (pin "2") (pinfunction "K_2") (pintype "passive"))
      (node (ref "R15") (pin "2") (pinfunction "2_2") (pintype "passive"))
    )
    (net (code "14") (name "Net-(D10-A)") (class "Default")
      (node (ref "D10") (pin "1") (pinfunction "A_1") (pintype "passive"))
      (node (ref "DZ2") (pin "2") (pinfunction "K_2") (pintype "passive"))
      (node (ref "Q4") (pin "4") (pinfunction "G_4") (pintype "passive"))
      (node (ref "R12") (pin "2") (pinfunction "2_2") (pintype "passive"))
      (node (ref "R18") (pin "2") (pinfunction "2_2") (pintype "passive"))
    )
    (net (code "15") (name "Net-(D10-K)") (class "Default")
      (node (ref "D10") (pin "2") (pinfunction "K_2") (pintype "passive"))
      (node (ref "R16") (pin "2") (pinfunction "2_2") (pintype "passive"))
    )
    (net (code "16") (name "Net-(D11-A)") (class "Default")
      (node (ref "C17") (pin "1") (pinfunction "1_1") (pintype "passive"))
      (node (ref "D11") (pin "1") (pinfunction "A_1") (pintype "passive"))
      (node (ref "D12") (pin "2") (pinfunction "K_2") (pintype "passive"))
      (node (ref "D5") (pin "1") (pinfunction "A_1") (pintype "passive"))
      (node (ref "DZ2") (pin "1") (pinfunction "A_1") (pintype "passive"))
      (node (ref "JP3") (pin "2") (pinfunction "2_2") (pintype "passive"))
      (node (ref "Q4") (pin "1") (pinfunction "S_1") (pintype "passive"))
      (node (ref "Q4") (pin "2") (pinfunction "S_2") (pintype "passive"))
      (node (ref "Q4") (pin "3") (pinfunction "S_3") (pintype "passive"))
      (node (ref "Q6") (pin "5") (pinfunction "D_5") (pintype "passive"))
      (node (ref "Q6") (pin "6") (pinfunction "D_6") (pintype "passive"))
      (node (ref "Q6") (pin "7") (pinfunction "D_7") (pintype "passive"))
      (node (ref "Q6") (pin "8") (pinfunction "D_8") (pintype "passive"))
      (node (ref "Q6") (pin "9") (pinfunction "D_9") (pintype "passive"))
      (node (ref "R18") (pin "1") (pinfunction "1_1") (pintype "passive"))
      (node (ref "U3") (pin "6") (pinfunction "VS_6") (pintype "passive"))
    )
    (net (code "17") (name "Net-(D11-K)") (class "Default")
      (node (ref "C16") (pin "1") (pinfunction "1_1") (pintype "passive"))
      (node (ref "D11") (pin "2") (pinfunction "K_2") (pintype "passive"))
      (node (ref "D13") (pin "2") (pinfunction "K_2") (pintype "passive"))
      (node (ref "D6") (pin "1") (pinfunction "A_1") (pintype "passive"))
      (node (ref "DZ1") (pin "1") (pinfunction "A_1") (pintype "passive"))
      (node (ref "JP3") (pin "1") (pinfunction "1_1") (pintype "passive"))
      (node (ref "Q3") (pin "1") (pinfunction "S_1") (pintype "passive"))
      (node (ref "Q3") (pin "2") (pinfunction "S_2") (pintype "passive"))
      (node (ref "Q3") (pin "3") (pinfunction "S_3") (pintype "passive"))
      (node (ref "Q5") (pin "5") (pinfunction "D_5") (pintype "passive"))
      (node (ref "Q5") (pin "6") (pinfunction "D_6") (pintype "passive"))
      (node (ref "Q5") (pin "7") (pinfunction "D_7") (pintype "passive"))
      (node (ref "Q5") (pin "8") (pinfunction "D_8") (pintype "passive"))
      (node (ref "Q5") (pin "9") (pinfunction "D_9") (pintype "passive"))
      (node (ref "R17") (pin "1") (pinfunction "1_1") (pintype "passive"))
      (node (ref "U2") (pin "6") (pinfunction "VS_6") (pintype "passive"))
    )
    (net (code "18") (name "Net-(D12-A)") (class "Default")
      (node (ref "D12") (pin "1") (pinfunction "A_1") (pintype "passive"))
      (node (ref "D13") (pin "1") (pinfunction "A_1") (pintype "passive"))
      (node (ref "DZ3") (pin "1") (pinfunction "A_1") (pintype "passive"))
      (node (ref "DZ4") (pin "1") (pinfunction "A_1") (pintype "passive"))
      (node (ref "Q5") (pin "1") (pinfunction "S_1") (pintype "passive"))
      (node (ref "Q5") (pin "2") (pinfunction "S_2") (pintype "passive"))
      (node (ref "Q5") (pin "3") (pinfunction "S_3") (pintype "passive"))
      (node (ref "Q6") (pin "1") (pinfunction "S_1") (pintype "passive"))
      (node (ref "Q6") (pin "2") (pinfunction "S_2") (pintype "passive"))
      (node (ref "Q6") (pin "3") (pinfunction "S_3") (pintype "passive"))
      (node (ref "R21") (pin "1") (pinfunction "1_1") (pintype "passive"))
      (node (ref "R22") (pin "1") (pinfunction "1_1") (pintype "passive"))
      (node (ref "R57") (pin "2") (pinfunction "2_2") (pintype "passive"))
      (node (ref "R63") (pin "2") (pinfunction "2_2") (pintype "passive"))
    )
    (net (code "19") (name "Net-(D14-A)") (class "Default")
      (node (ref "D14") (pin "1") (pinfunction "A_1") (pintype "passive"))
      (node (ref "DZ3") (pin "2") (pinfunction "K_2") (pintype "passive"))
      (node (ref "Q5") (pin "4") (pinfunction "G_4") (pintype "passive"))
      (node (ref "R21") (pin "2") (pinfunction "2_2") (pintype "passive"))
      (node (ref "R24") (pin "2") (pinfunction "2_2") (pintype "passive"))
    )
    (net (code "20") (name "Net-(D14-K)") (class "Default")
      (node (ref "D14") (pin "2") (pinfunction "K_2") (pintype "passive"))
      (node (ref "R19") (pin "2") (pinfunction "2_2") (pintype "passive"))
    )
    (net (code "21") (name "Net-(D15-A)") (class "Default")
      (node (ref "D15") (pin "1") (pinfunction "A_1") (pintype "passive"))
      (node (ref "DZ4") (pin "2") (pinfunction "K_2") (pintype "passive"))
      (node (ref "Q6") (pin "4") (pinfunction "G_4") (pintype "passive"))
      (node (ref "R22") (pin "2") (pinfunction "2_2") (pintype "passive"))
      (node (ref "R23") (pin "2") (pinfunction "2_2") (pintype "passive"))
    )
    (net (code "22") (name "Net-(D15-K)") (class "Default")
      (node (ref "D15") (pin "2") (pinfunction "K_2") (pintype "passive"))
      (node (ref "R20") (pin "2") (pinfunction "2_2") (pintype "passive"))
    )
    (net (code "23") (name "Net-(D16-A)") (class "Default")
      (node (ref "C23") (pin "1") (pinfunction "1_1") (pintype "passive"))
      (node (ref "D16") (pin "1") (pinfunction "A_1") (pintype "passive"))
      (node (ref "D22") (pin "1") (pinfunction "A_1") (pintype "passive"))
      (node (ref "D23") (pin "2") (pinfunction "K_2") (pintype "passive"))
      (node (ref "DZ6") (pin "1") (pinfunction "A_1") (pintype "passive"))
      (node (ref "JP4") (pin "2") (pinfunction "2_2") (pintype "passive"))
      (node (ref "Q10") (pin "5") (pinfunction "D_5") (pintype "passive"))
      (node (ref "Q10") (pin "6") (pinfunction "D_6") (pintype "passive"))
      (node (ref "Q10") (pin "7") (pinfunction "D_7") (pintype "passive"))
      (node (ref "Q10") (pin "8") (pinfunction "D_8") (pintype "passive"))
      (node (ref "Q10") (pin "9") (pinfunction "D_9") (pintype "passive"))
      (node (ref "Q8") (pin "1") (pinfunction "S_1") (pintype "passive"))
      (node (ref "Q8") (pin "2") (pinfunction "S_2") (pintype "passive"))
      (node (ref "Q8") (pin "3") (pinfunction "S_3") (pintype "passive"))
      (node (ref "R32") (pin "1") (pinfunction "1_1") (pintype "passive"))
      (node (ref "U5") (pin "6") (pinfunction "VS_6") (pintype "passive"))
    )
    (net (code "24") (name "Net-(D17-A)") (class "Default")
      (node (ref "C22") (pin "1") (pinfunction "1_1") (pintype "passive"))
      (node (ref "D17") (pin "1") (pinfunction "A_1") (pintype "passive"))
      (node (ref "D22") (pin "2") (pinfunction "K_2") (pintype "passive"))
      (node (ref "D24") (pin "2") (pinfunction "K_2") (pintype "passive"))
      (node (ref "DZ5") (pin "1") (pinfunction "A_1") (pintype "passive"))
      (node (ref "JP4") (pin "1") (pinfunction "1_1") (pintype "passive"))
      (node (ref "Q7") (pin "1") (pinfunction "S_1") (pintype "passive"))
      (node (ref "Q7") (pin "2") (pinfunction "S_2") (pintype "passive"))
      (node (ref "Q7") (pin "3") (pinfunction "S_3") (pintype "passive"))
      (node (ref "Q9") (pin "5") (pinfunction "D_5") (pintype "passive"))
      (node (ref "Q9") (pin "6") (pinfunction "D_6") (pintype "passive"))
      (node (ref "Q9") (pin "7") (pinfunction "D_7") (pintype "passive"))
      (node (ref "Q9") (pin "8") (pinfunction "D_8") (pintype "passive"))
      (node (ref "Q9") (pin "9") (pinfunction "D_9") (pintype "passive"))
      (node (ref "R31") (pin "1") (pinfunction "1_1") (pintype "passive"))
      (node (ref "U4") (pin "6") (pinfunction "VS_6") (pintype "passive"))
    )
    (net (code "25") (name "Net-(D18-A)") (class "Default")
      (node (ref "D18") (pin "1") (pinfunction "A_1") (pintype "passive"))
      (node (ref "R27") (pin "2") (pinfunction "2_2") (pintype "passive"))
    )
    (net (code "26") (name "Net-(D18-K)") (class "Default")
      (node (ref "C22") (pin "2") (pinfunction "2_2") (pintype "passive"))
      (node (ref "D18") (pin "2") (pinfunction "K_2") (pintype "passive"))
      (node (ref "U4") (pin "8") (pinfunction "VB_8") (pintype "passive"))
    )
    (net (code "27") (name "Net-(D19-A)") (class "Default")
      (node (ref "D19") (pin "1") (pinfunction "A_1") (pintype "passive"))
      (node (ref "R28") (pin "2") (pinfunction "2_2") (pintype "passive"))
    )
    (net (code "28") (name "Net-(D19-K)") (class "Default")
      (node (ref "C23") (pin "2") (pinfunction "2_2") (pintype "passive"))
      (node (ref "D19") (pin "2") (pinfunction "K_2") (pintype "passive"))
      (node (ref "U5") (pin "8") (pinfunction "VB_8") (pintype "passive"))
    )
    (net (code "29") (name "Net-(D20-A)") (class "Default")
      (node (ref "D20") (pin "1") (pinfunction "A_1") (pintype "passive"))
      (node (ref "DZ5") (pin "2") (pinfunction "K_2") (pintype "passive"))
      (node (ref "Q7") (pin "4") (pinfunction "G_4") (pintype "passive"))
      (node (ref "R25") (pin "2") (pinfunction "2_2") (pintype "passive"))
      (node (ref "R31") (pin "2") (pinfunction "2_2") (pintype "passive"))
    )
    (net (code "30") (name "Net-(D20-K)") (class "Default")
      (node (ref "D20") (pin "2") (pinfunction "K_2") (pintype "passive"))
      (node (ref "R29") (pin "2") (pinfunction "2_2") (pintype "passive"))
    )
    (net (code "31") (name "Net-(D21-A)") (class "Default")
      (node (ref "D21") (pin "1") (pinfunction "A_1") (pintype "passive"))
      (node (ref "DZ6") (pin "2") (pinfunction "K_2") (pintype "passive"))
      (node (ref "Q8") (pin "4") (pinfunction "G_4") (pintype "passive"))
      (node (ref "R26") (pin "2") (pinfunction "2_2") (pintype "passive"))
      (node (ref "R32") (pin "2") (pinfunction "2_2") (pintype "passive"))
    )
    (net (code "32") (name "Net-(D21-K)") (class "Default")
      (node (ref "D21") (pin "2") (pinfunction "K_2") (pintype "passive"))
      (node (ref "R30") (pin "2") (pinfunction "2_2") (pintype "passive"))
    )
    (net (code "33") (name "Net-(D23-A)") (class "Default")
      (node (ref "D23") (pin "1") (pinfunction "A_1") (pintype "passive"))
      (node (ref "D24") (pin "1") (pinfunction "A_1") (pintype "passive"))
      (node (ref "DZ7") (pin "1") (pinfunction "A_1") (pintype "passive"))
      (node (ref "DZ8") (pin "1") (pinfunction "A_1") (pintype "passive"))
      (node (ref "Q10") (pin "1") (pinfunction "S_1") (pintype "passive"))
      (node (ref "Q10") (pin "2") (pinfunction "S_2") (pintype "passive"))
      (node (ref "Q10") (pin "3") (pinfunction "S_3") (pintype "passive"))
      (node (ref "Q9") (pin "1") (pinfunction "S_1") (pintype "passive"))
      (node (ref "Q9") (pin "2") (pinfunction "S_2") (pintype "passive"))
      (node (ref "Q9") (pin "3") (pinfunction "S_3") (pintype "passive"))
      (node (ref "R35") (pin "1") (pinfunction "1_1") (pintype "passive"))
      (node (ref "R36") (pin "1") (pinfunction "1_1") (pintype "passive"))
      (node (ref "R71") (pin "2") (pinfunction "2_2") (pintype "passive"))
      (node (ref "R75") (pin "2") (pinfunction "2_2") (pintype "passive"))
    )
    (net (code "34") (name "Net-(D25-A)") (class "Default")
      (node (ref "D25") (pin "1") (pinfunction "A_1") (pintype "passive"))
      (node (ref "DZ7") (pin "2") (pinfunction "K_2") (pintype "passive"))
      (node (ref "Q9") (pin "4") (pinfunction "G_4") (pintype "passive"))
      (node (ref "R35") (pin "2") (pinfunction "2_2") (pintype "passive"))
      (node (ref "R37") (pin "2") (pinfunction "2_2") (pintype "passive"))
    )
    (net (code "35") (name "Net-(D25-K)") (class "Default")
      (node (ref "D25") (pin "2") (pinfunction "K_2") (pintype "passive"))
      (node (ref "R33") (pin "2") (pinfunction "2_2") (pintype "passive"))
    )
    (net (code "36") (name "Net-(D26-A)") (class "Default")
      (node (ref "D26") (pin "1") (pinfunction "A_1") (pintype "passive"))
      (node (ref "DZ8") (pin "2") (pinfunction "K_2") (pintype "passive"))
      (node (ref "Q10") (pin "4") (pinfunction "G_4") (pintype "passive"))
      (node (ref "R36") (pin "2") (pinfunction "2_2") (pintype "passive"))
      (node (ref "R38") (pin "2") (pinfunction "2_2") (pintype "passive"))
    )
    (net (code "37") (name "Net-(D26-K)") (class "Default")
      (node (ref "D26") (pin "2") (pinfunction "K_2") (pintype "passive"))
      (node (ref "R34") (pin "2") (pinfunction "2_2") (pintype "passive"))
    )
    (net (code "38") (name "Net-(D27-A)") (class "Default")
      (node (ref "D27") (pin "1") (pinfunction "A_1") (pintype "passive"))
      (node (ref "IC1") (pin "1") (pinfunction "SW_1") (pintype "passive"))
      (node (ref "L2") (pin "1") (pinfunction "1_1") (pintype "passive"))
    )
    (net (code "39") (name "Net-(IC1-EN)") (class "Default")
      (node (ref "C32") (pin "1") (pinfunction "1_1") (pintype "passive"))
      (node (ref "IC1") (pin "4") (pinfunction "EN_4") (pintype "passive"))
      (node (ref "IC1") (pin "5") (pinfunction "VCC_5") (pintype "passive"))
      (node (ref "L2") (pin "2") (pinfunction "2_2") (pintype "passive"))
      (node (ref "L3") (pin "2") (pinfunction "2_2") (pintype "passive"))
    )
    (net (code "40") (name "Net-(IC1-FB)") (class "Default")
      (node (ref "C30") (pin "2") (pinfunction "2_2") (pintype "passive"))
      (node (ref "IC1") (pin "3") (pinfunction "FB_3") (pintype "passive"))
      (node (ref "R43") (pin "2") (pinfunction "2_2") (pintype "passive"))
      (node (ref "R44") (pin "1") (pinfunction "1_1") (pintype "passive"))
    )
    (net (code "41") (name "Net-(IC2A-IN+)") (class "Default")
      (node (ref "IC2") (pin "3") (pinfunction "IN+_3") (pintype "input"))
      (node (ref "R70") (pin "2") (pinfunction "2_2") (pintype "passive"))
      (node (ref "R71") (pin "1") (pinfunction "1_1") (pintype "passive"))
    )
    (net (code "42") (name "Net-(IC2A-IN-)") (class "Default")
      (node (ref "IC2") (pin "2") (pinfunction "IN-_2") (pintype "input"))
      (node (ref "R76") (pin "1") (pinfunction "1_1") (pintype "passive"))
      (node (ref "R77") (pin "2") (pinfunction "2_2") (pintype "passive"))
    )
    (net (code "43") (name "Net-(IC2A-OUT)") (class "Default")
      (node (ref "IC2") (pin "1") (pinfunction "OUT_1") (pintype "output"))
      (node (ref "R74") (pin "2") (pinfunction "2_2") (pintype "passive"))
      (node (ref "R77") (pin "1") (pinfunction "1_1") (pintype "passive"))
    )
    (net (code "44") (name "Net-(IC2B-IN+)") (class "Default")
      (node (ref "IC2") (pin "5") (pinfunction "IN+_5") (pintype "input"))
      (node (ref "R51") (pin "2") (pinfunction "2_2") (pintype "passive"))
      (node (ref "R57") (pin "1") (pinfunction "1_1") (pintype "passive"))
    )
    (net (code "45") (name "Net-(IC2B-IN-)") (class "Default")
      (node (ref "IC2") (pin "6") (pinfunction "IN-_6") (pintype "input"))
      (node (ref "R64") (pin "1") (pinfunction "1_1") (pintype "passive"))
      (node (ref "R65") (pin "2") (pinfunction "2_2") (pintype "passive"))
    )
    (net (code "46") (name "Net-(IC2B-OUT)") (class "Default")
      (node (ref "IC2") (pin "7") (pinfunction "OUT_7") (pintype "output"))
      (node (ref "R62") (pin "2") (pinfunction "2_2") (pintype "passive"))
      (node (ref "R65") (pin "1") (pinfunction "1_1") (pintype "passive"))
    )
    (net (code "47") (name "Net-(R48-Pad2)") (class "Default")
      (node (ref "R48") (pin "2") (pinfunction "2_2") (pintype "passive"))
      (node (ref "S2") (pin "2") (pinfunction "2_2") (pintype "passive"))
    )
    (net (code "48") (name "Net-(U2-HO)") (class "Default")
      (node (ref "R11") (pin "1") (pinfunction "1_1") (pintype "passive"))
      (node (ref "R15") (pin "1") (pinfunction "1_1") (pintype "passive"))
      (node (ref "U2") (pin "7") (pinfunction "HO_7") (pintype "passive"))
    )
    (net (code "49") (name "Net-(U2-LO)") (class "Default")
      (node (ref "R19") (pin "1") (pinfunction "1_1") (pintype "passive"))
      (node (ref "R24") (pin "1") (pinfunction "1_1") (pintype "passive"))
      (node (ref "U2") (pin "5") (pinfunction "LO_5") (pintype "passive"))
    )
    (net (code "50") (name "Net-(U3-HO)") (class "Default")
      (node (ref "R12") (pin "1") (pinfunction "1_1") (pintype "passive"))
      (node (ref "R16") (pin "1") (pinfunction "1_1") (pintype "passive"))
      (node (ref "U3") (pin "7") (pinfunction "HO_7") (pintype "passive"))
    )
    (net (code "51") (name "Net-(U3-LO)") (class "Default")
      (node (ref "R20") (pin "1") (pinfunction "1_1") (pintype "passive"))
      (node (ref "R23") (pin "1") (pinfunction "1_1") (pintype "passive"))
      (node (ref "U3") (pin "5") (pinfunction "LO_5") (pintype "passive"))
    )
    (net (code "52") (name "Net-(U4-HO)") (class "Default")
      (node (ref "R25") (pin "1") (pinfunction "1_1") (pintype "passive"))
      (node (ref "R29") (pin "1") (pinfunction "1_1") (pintype "passive"))
      (node (ref "U4") (pin "7") (pinfunction "HO_7") (pintype "passive"))
    )
    (net (code "53") (name "Net-(U4-LO)") (class "Default")
      (node (ref "R33") (pin "1") (pinfunction "1_1") (pintype "passive"))
      (node (ref "R37") (pin "1") (pinfunction "1_1") (pintype "passive"))
      (node (ref "U4") (pin "5") (pinfunction "LO_5") (pintype "passive"))
    )
    (net (code "54") (name "Net-(U5-HO)") (class "Default")
      (node (ref "R26") (pin "1") (pinfunction "1_1") (pintype "passive"))
      (node (ref "R30") (pin "1") (pinfunction "1_1") (pintype "passive"))
      (node (ref "U5") (pin "7") (pinfunction "HO_7") (pintype "passive"))
    )
    (net (code "55") (name "Net-(U5-LO)") (class "Default")
      (node (ref "R34") (pin "1") (pinfunction "1_1") (pintype "passive"))
      (node (ref "R38") (pin "1") (pinfunction "1_1") (pintype "passive"))
      (node (ref "U5") (pin "5") (pinfunction "LO_5") (pintype "passive"))
    )
    (net (code "56") (name "Net-(U6-A)") (class "Default")
      (node (ref "R45") (pin "1") (pinfunction "1_1") (pintype "passive"))
      (node (ref "U6") (pin "1") (pinfunction "A_1") (pintype "passive"))
    )
    (net (code "57") (name "Net-(U6-B)") (class "Default")
      (node (ref "R48") (pin "1") (pinfunction "1_1") (pintype "passive"))
      (node (ref "R59") (pin "1") (pinfunction "1_1") (pintype "passive"))
      (node (ref "U6") (pin "2") (pinfunction "B_2") (pintype "passive"))
    )
    (net (code "58") (name "Net-(U6-Y)") (class "Default")
      (node (ref "R46") (pin "1") (pinfunction "1_1") (pintype "passive"))
      (node (ref "U6") (pin "4") (pinfunction "Y_4") (pintype "passive"))
    )
    (net (code "59") (name "PGND") (class "Default")
      (node (ref "C18") (pin "1") (pinfunction "1_1") (pintype "passive"))
      (node (ref "C19") (pin "1") (pinfunction "1_1") (pintype "passive"))
      (node (ref "C20") (pin "1") (pinfunction "1_1") (pintype "passive"))
      (node (ref "C21") (pin "1") (pinfunction "1_1") (pintype "passive"))
      (node (ref "C24") (pin "1") (pinfunction "1_1") (pintype "passive"))
      (node (ref "C25") (pin "1") (pinfunction "1_1") (pintype "passive"))
      (node (ref "C26") (pin "1") (pinfunction "1_1") (pintype "passive"))
      (node (ref "C27") (pin "1") (pinfunction "1_1") (pintype "passive"))
      (node (ref "C28") (pin "2") (pinfunction "2_2") (pintype "passive"))
      (node (ref "C29") (pin "2") (pinfunction "2_2") (pintype "passive"))
      (node (ref "C31") (pin "2") (pinfunction "2_2") (pintype "passive"))
      (node (ref "C32") (pin "2") (pinfunction "2_2") (pintype "passive"))
      (node (ref "IC1") (pin "2") (pinfunction "GND_2") (pintype "passive"))
      (node (ref "R44") (pin "2") (pinfunction "2_2") (pintype "passive"))
      (node (ref "R63") (pin "1") (pinfunction "1_1") (pintype "passive"))
      (node (ref "R64") (pin "2") (pinfunction "2_2") (pintype "passive"))
      (node (ref "R75") (pin "1") (pinfunction "1_1") (pintype "passive"))
      (node (ref "R76") (pin "2") (pinfunction "2_2") (pintype "passive"))
      (node (ref "U2") (pin "4") (pinfunction "GND_4") (pintype "passive"))
      (node (ref "U3") (pin "4") (pinfunction "GND_4") (pintype "passive"))
      (node (ref "U4") (pin "4") (pinfunction "GND_4") (pintype "passive"))
      (node (ref "U5") (pin "4") (pinfunction "GND_4") (pintype "passive"))
    )
    (net (code "60") (name "PWM1") (class "Default")
      (node (ref "U2") (pin "2") (pinfunction "IN_2") (pintype "passive"))
    )
    (net (code "61") (name "PWM2") (class "Default")
      (node (ref "U3") (pin "2") (pinfunction "IN_2") (pintype "passive"))
    )
    (net (code "62") (name "PWM3") (class "Default")
      (node (ref "U4") (pin "2") (pinfunction "IN_2") (pintype "passive"))
    )
    (net (code "63") (name "PWM4") (class "Default")
      (node (ref "U5") (pin "2") (pinfunction "IN_2") (pintype "passive"))
    )
    (net (code "64") (name "SD1") (class "Default")
      (node (ref "R46") (pin "2") (pinfunction "2_2") (pintype "passive"))
      (node (ref "R47") (pin "1") (pinfunction "1_1") (pintype "passive"))
      (node (ref "U2") (pin "3") (pinfunction "SD#_3") (pintype "passive"))
      (node (ref "U3") (pin "3") (pinfunction "SD#_3") (pintype "passive"))
      (node (ref "U4") (pin "3") (pinfunction "SD#_3") (pintype "passive"))
      (node (ref "U5") (pin "3") (pinfunction "SD#_3") (pintype "passive"))
    )
    (net (code "65") (name "VOUT") (class "Default")
      (node (ref "C31") (pin "1") (pinfunction "1_1") (pintype "passive"))
      (node (ref "D16") (pin "2") (pinfunction "K_2") (pintype "passive"))
      (node (ref "D17") (pin "2") (pinfunction "K_2") (pintype "passive"))
      (node (ref "D5") (pin "2") (pinfunction "K_2") (pintype "passive"))
      (node (ref "D6") (pin "2") (pinfunction "K_2") (pintype "passive"))
      (node (ref "L3") (pin "1") (pinfunction "1_1") (pintype "passive"))
      (node (ref "Q3") (pin "5") (pinfunction "D_5") (pintype "passive"))
      (node (ref "Q3") (pin "6") (pinfunction "D_6") (pintype "passive"))
      (node (ref "Q3") (pin "7") (pinfunction "D_7") (pintype "passive"))
      (node (ref "Q3") (pin "8") (pinfunction "D_8") (pintype "passive"))
      (node (ref "Q3") (pin "9") (pinfunction "D_9") (pintype "passive"))
      (node (ref "Q4") (pin "5") (pinfunction "D_5") (pintype "passive"))
      (node (ref "Q4") (pin "6") (pinfunction "D_6") (pintype "passive"))
      (node (ref "Q4") (pin "7") (pinfunction "D_7") (pintype "passive"))
      (node (ref "Q4") (pin "8") (pinfunction "D_8") (pintype "passive"))
      (node (ref "Q4") (pin "9") (pinfunction "D_9") (pintype "passive"))
      (node (ref "Q7") (pin "5") (pinfunction "D_5") (pintype "passive"))
      (node (ref "Q7") (pin "6") (pinfunction "D_6") (pintype "passive"))
      (node (ref "Q7") (pin "7") (pinfunction "D_7") (pintype "passive"))
      (node (ref "Q7") (pin "8") (pinfunction "D_8") (pintype "passive"))
      (node (ref "Q7") (pin "9") (pinfunction "D_9") (pintype "passive"))
      (node (ref "Q8") (pin "5") (pinfunction "D_5") (pintype "passive"))
      (node (ref "Q8") (pin "6") (pinfunction "D_6") (pintype "passive"))
      (node (ref "Q8") (pin "7") (pinfunction "D_7") (pintype "passive"))
      (node (ref "Q8") (pin "8") (pinfunction "D_8") (pintype "passive"))
      (node (ref "Q8") (pin "9") (pinfunction "D_9") (pintype "passive"))
    )
    (net (code "66") (name "unconnected-(IC1-NC-Pad6)") (class "Default")
      (node (ref "IC1") (pin "6") (pinfunction "NC_6") (pintype "passive"))
    )
  )
)
